# Connector.net
KiCad netlist of a schematic drawn in Altium Designer
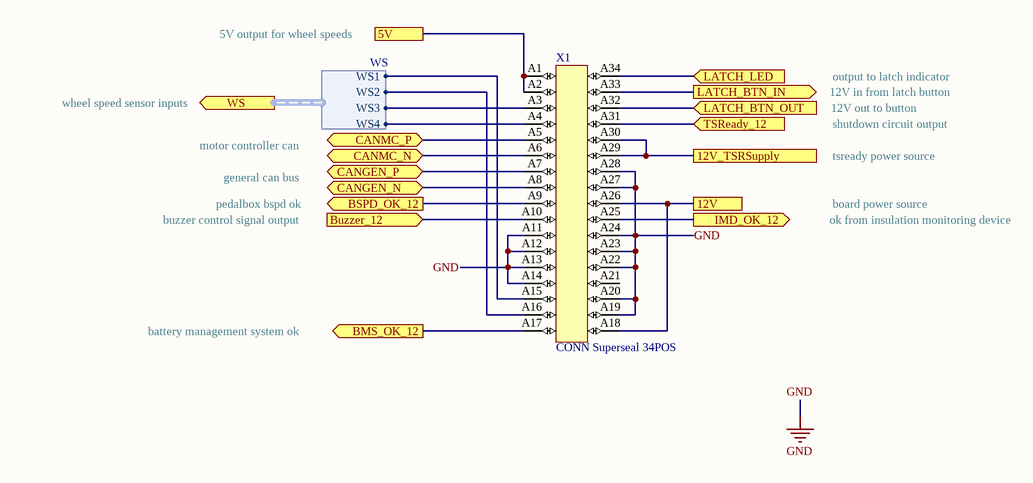
[diagram p0: Connector.SchDoc]

(export (version "E")
  (design (tool "Eeschema 10.0.6"))
  (components
    (comp (ref "X1")
      (value "CONN Superseal 34POS")
      (footprint "Superseal 34POS")
      (description "AMP Superseal 34 POS")
      (libsource (lib "altlib") (part "CONN Superseal 34POS"))
    )
  )
  (nets
    (net (code "2") (name "/5V") (class "Default")
      (node (ref "X1") (pin "A1") (pintype "bidirectional"))
      (node (ref "X1") (pin "A2") (pintype "bidirectional"))
    )
    (net (code "3") (name "/12V") (class "Default")
      (node (ref "X1") (pin "A18") (pintype "bidirectional"))
      (node (ref "X1") (pin "A26") (pintype "bidirectional"))
    )
    (net (code "4") (name "/12V_TSRSupply") (class "Default")
      (node (ref "X1") (pin "A29") (pintype "bidirectional"))
      (node (ref "X1") (pin "A30") (pintype "bidirectional"))
    )
    (net (code "5") (name "/BMS_OK_12") (class "Default")
      (node (ref "X1") (pin "A17") (pintype "bidirectional"))
    )
    (net (code "6") (name "/BSPD_OK_12") (class "Default")
      (node (ref "X1") (pin "A9") (pintype "bidirectional"))
    )
    (net (code "7") (name "/Buzzer_12") (class "Default")
      (node (ref "X1") (pin "A10") (pintype "bidirectional"))
    )
    (net (code "8") (name "/CANGEN_N") (class "Default")
      (node (ref "X1") (pin "A8") (pintype "bidirectional"))
    )
    (net (code "9") (name "/CANGEN_P") (class "Default")
      (node (ref "X1") (pin "A7") (pintype "bidirectional"))
    )
    (net (code "10") (name "/CANMC_N") (class "Default")
      (node (ref "X1") (pin "A6") (pintype "bidirectional"))
    )
    (net (code "11") (name "/CANMC_P") (class "Default")
      (node (ref "X1") (pin "A5") (pintype "bidirectional"))
    )
    (net (code "12") (name "/IMD_OK_12") (class "Default")
      (node (ref "X1") (pin "A25") (pintype "bidirectional"))
    )
    (net (code "13") (name "/LATCH_BTN_IN") (class "Default")
      (node (ref "X1") (pin "A33") (pintype "bidirectional"))
    )
    (net (code "14") (name "/LATCH_BTN_OUT") (class "Default")
      (node (ref "X1") (pin "A32") (pintype "bidirectional"))
    )
    (net (code "15") (name "/LATCH_LED") (class "Default")
      (node (ref "X1") (pin "A34") (pintype "bidirectional"))
    )
    (net (code "16") (name "/TSReady_12") (class "Default")
      (node (ref "X1") (pin "A31") (pintype "bidirectional"))
    )
    (net (code "17") (name "/WS1") (class "Default") (node (ref "X1") (pin "A15") (pintype "bidirectional")))
    (net (code "18") (name "/WS2") (class "Default") (node (ref "X1") (pin "A16") (pintype "bidirectional")))
    (net (code "19") (name "/WS3") (class "Default") (node (ref "X1") (pin "A3") (pintype "bidirectional")))
    (net (code "20") (name "/WS4") (class "Default") (node (ref "X1") (pin "A4") (pintype "bidirectional")))
    (net (code "22") (name "GND") (class "Default")
      (node (ref "X1") (pin "A11") (pintype "bidirectional"))
      (node (ref "X1") (pin "A12") (pintype "bidirectional"))
      (node (ref "X1") (pin "A13") (pintype "bidirectional"))
      (node (ref "X1") (pin "A14") (pintype "bidirectional"))
      (node (ref "X1") (pin "A19") (pintype "bidirectional"))
      (node (ref "X1") (pin "A20") (pintype "bidirectional"))
      (node (ref "X1") (pin "A22") (pintype "bidirectional"))
      (node (ref "X1") (pin "A23") (pintype "bidirectional"))
      (node (ref "X1") (pin "A24") (pintype "bidirectional"))
      (node (ref "X1") (pin "A27") (pintype "bidirectional"))
      (node (ref "X1") (pin "A28") (pintype "bidirectional"))
    )
    (net (code "23") (name "unconnected-(X1-PadA21)") (class "Default")
      (node (ref "X1") (pin "A21") (pintype "bidirectional"))
    )
  )
)
